# Buzzer.net
KiCad netlist of a schematic drawn in EAGLE
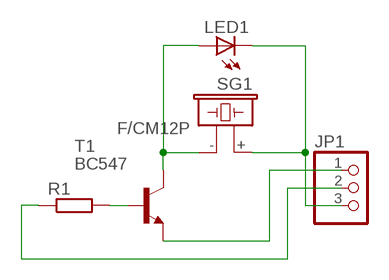
[diagram p0: schematic, sheet 1]

(export (version "E")
  (design (tool "Eeschema 10.0.6"))
  (components
    (comp (ref "JP1")
      (value "PINHD-1X3")
      (footprint "eagle-import:1X03")
      (libsource (lib "eagle-import") (part "PINHD-1X3"))
    )
    (comp (ref "LED1")
      (value "LED3MM")
      (footprint "eagle-import:LED3MM")
      (libsource (lib "eagle-import") (part "LED3MM"))
    )
    (comp (ref "R1")
      (value "R-EU_0204/7")
      (footprint "eagle-import:0204_7")
      (libsource (lib "eagle-import") (part "R-EU_0204/7"))
    )
    (comp (ref "SG1")
      (value "F/CM12P")
      (footprint "eagle-import:F_CM12P")
      (libsource (lib "eagle-import") (part "F/CM12P"))
    )
    (comp (ref "T1")
      (value "BC547")
      (footprint "eagle-import:TO92")
      (libsource (lib "eagle-import") (part "BC547"))
    )
  )
  (nets
    (net (code "1") (name "Net-(JP1-Pad2)") (class "Default")
      (node (ref "JP1") (pin "2") (pinfunction "2_2") (pintype "passive"))
      (node (ref "R1") (pin "1") (pinfunction "1_1") (pintype "passive"))
    )
    (net (code "2") (name "Net-(LED1-C)") (class "Default")
      (node (ref "JP1") (pin "3") (pinfunction "3_3") (pintype "passive"))
      (node (ref "LED1") (pin "K") (pinfunction "C_K") (pintype "passive"))
      (node (ref "SG1") (pin "+") (pinfunction "1_+") (pintype "passive"))
    )
    (net (code "3") (name "Net-(SG1-2)") (class "Default")
      (node (ref "LED1") (pin "A") (pinfunction "A_A") (pintype "passive"))
      (node (ref "SG1") (pin "-") (pinfunction "2_-") (pintype "passive"))
      (node (ref "T1") (pin "3") (pinfunction "C_3") (pintype "passive"))
    )
    (net (code "4") (name "Net-(T1-B)") (class "Default")
      (node (ref "R1") (pin "2") (pinfunction "2_2") (pintype "passive"))
      (node (ref "T1") (pin "2") (pinfunction "B_2") (pintype "passive"))
    )
    (net (code "5") (name "Net-(T1-E)") (class "Default")
      (node (ref "JP1") (pin "1") (pinfunction "1_1") (pintype "passive"))
      (node (ref "T1") (pin "1") (pinfunction "E_1") (pintype "passive"))
    )
  )
)
